# untitled.net
KiCad netlist of a schematic drawn in EAGLE
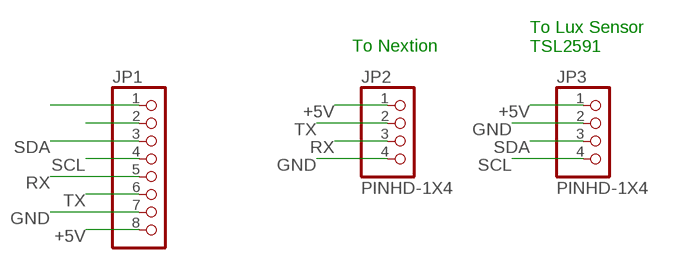
[diagram p0: schematic, sheet 1]

(export (version "E")
  (design (tool "Eeschema 10.0.6"))
  (components
    (comp (ref "JP1")
      (value "PINHD-1X8BIG")
      (footprint "eagle-import:1X08-BIG")
      (libsource (lib "eagle-import") (part "PINHD-1X8BIG"))
    )
    (comp (ref "JP2")
      (value "PINHD-1X4")
      (footprint "eagle-import:1X04")
      (libsource (lib "eagle-import") (part "PINHD-1X4"))
    )
    (comp (ref "JP3")
      (value "PINHD-1X4")
      (footprint "eagle-import:1X04")
      (libsource (lib "eagle-import") (part "PINHD-1X4"))
    )
  )
  (nets
    (net (code "1") (name "/+5V") (class "Default")
      (node (ref "JP1") (pin "8") (pinfunction "8_8") (pintype "passive"))
      (node (ref "JP2") (pin "1") (pinfunction "1_1") (pintype "passive"))
      (node (ref "JP3") (pin "1") (pinfunction "1_1") (pintype "passive"))
    )
    (net (code "2") (name "/GND") (class "Default")
      (node (ref "JP1") (pin "7") (pinfunction "7_7") (pintype "passive"))
      (node (ref "JP2") (pin "4") (pinfunction "4_4") (pintype "passive"))
      (node (ref "JP3") (pin "2") (pinfunction "2_2") (pintype "passive"))
    )
    (net (code "3") (name "/RX") (class "Default")
      (node (ref "JP1") (pin "5") (pinfunction "5_5") (pintype "passive"))
      (node (ref "JP2") (pin "3") (pinfunction "3_3") (pintype "passive"))
    )
    (net (code "4") (name "/SCL") (class "Default")
      (node (ref "JP1") (pin "4") (pinfunction "4_4") (pintype "passive"))
      (node (ref "JP3") (pin "4") (pinfunction "4_4") (pintype "passive"))
    )
    (net (code "5") (name "/SDA") (class "Default")
      (node (ref "JP1") (pin "3") (pinfunction "3_3") (pintype "passive"))
      (node (ref "JP3") (pin "3") (pinfunction "3_3") (pintype "passive"))
    )
    (net (code "6") (name "/TX") (class "Default")
      (node (ref "JP1") (pin "6") (pinfunction "6_6") (pintype "passive"))
      (node (ref "JP2") (pin "2") (pinfunction "2_2") (pintype "passive"))
    )
    (net (code "7") (name "unconnected-(JP1-Pad1)") (class "Default")
      (node (ref "JP1") (pin "1") (pinfunction "1_1") (pintype "passive"))
    )
    (net (code "8") (name "unconnected-(JP1-Pad2)") (class "Default")
      (node (ref "JP1") (pin "2") (pinfunction "2_2") (pintype "passive"))
    )
  )
)
